# Ethernet.net
KiCad netlist of a schematic drawn in Altium Designer
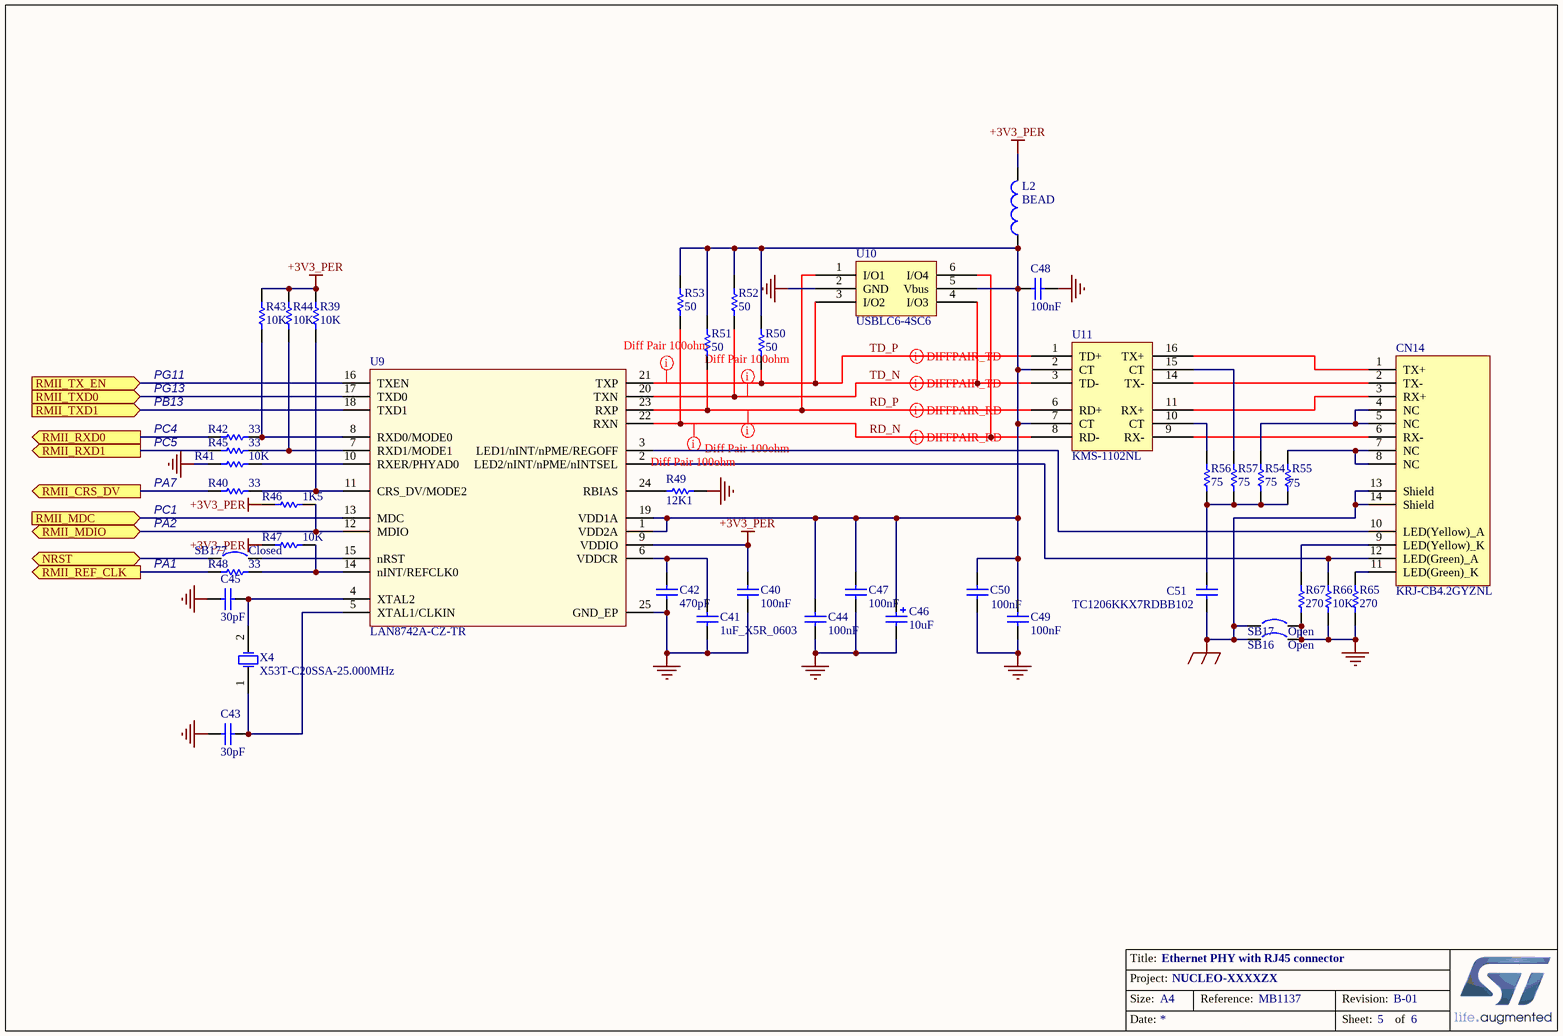
[diagram p0: Ethernet.SchDoc]

(export (version "E")
  (design (tool "Eeschema 10.0.6"))
  (components
    (comp (ref "C40")
      (value "100nF")
      (footprint "0603C")
      (description "Capacitor 0402 / 0603 / 0805")
      (libsource (lib "MCD_TOOLS") (part "Capacitor_ST"))
    )
    (comp (ref "C41")
      (value "1uF_X5R_0603")
      (footprint "0603C")
      (description "0603  X5R 1µF")
      (fields (field (name "TOLERANCE") "10%"))
      (libsource (lib "MB963_1") (part "CAP SMD 0603  X5R 1µF 25V 10%"))
    )
    (comp (ref "C42")
      (value "470pF")
      (footprint "0603C")
      (description "Capacitor 0402 / 0603 / 0805")
      (libsource (lib "MCD_TOOLS") (part "Capacitor_ST"))
    )
    (comp (ref "C43")
      (value "30pF")
      (footprint "0603C")
      (description "Capacitor 0402 / 0603 / 0805")
      (libsource (lib "MCD_TOOLS") (part "Capacitor_ST"))
    )
    (comp (ref "C44")
      (value "100nF")
      (footprint "0603C")
      (description "Capacitor 0402 / 0603 / 0805")
      (libsource (lib "MCD_TOOLS") (part "Capacitor_ST"))
    )
    (comp (ref "C45")
      (value "30pF")
      (footprint "0603C")
      (description "Capacitor 0402 / 0603 / 0805")
      (libsource (lib "MCD_TOOLS") (part "Capacitor_ST"))
    )
    (comp (ref "C46")
      (value "10uF")
      (footprint "TAN-A")
      (description "Polarized Capacitor,10uF,10V,10%,typeA,VISHAY")
      (libsource (lib "MCD_TOOLS") (part "Cap_10uF_POL_10%_TANA"))
    )
    (comp (ref "C47")
      (value "100nF")
      (footprint "0603C")
      (description "Capacitor 0402 / 0603 / 0805")
      (libsource (lib "MCD_TOOLS") (part "Capacitor_ST"))
    )
    (comp (ref "C48")
      (value "100nF")
      (footprint "0603C")
      (description "Capacitor 0402 / 0603 / 0805")
      (libsource (lib "MCD_TOOLS") (part "Capacitor_ST"))
    )
    (comp (ref "C49")
      (value "100nF")
      (footprint "0603C")
      (description "Capacitor 0402 / 0603 / 0805")
      (libsource (lib "MCD_TOOLS") (part "Capacitor_ST"))
    )
    (comp (ref "C50")
      (value "100nF")
      (footprint "0603C")
      (description "Capacitor 0402 / 0603 / 0805")
      (libsource (lib "MCD_TOOLS") (part "Capacitor_ST"))
    )
    (comp (ref "C51")
      (value "TC1206KKX7RDBB102")
      (footprint "1206C")
      (description "Capacitor 0402 / 0603 / 0805/ 1206")
      (libsource (lib "MCD_TOOLS") (part "Capacitor_ST"))
    )
    (comp (ref "CN14")
      (value "KRJ-CB4.2GYZNL")
      (footprint "RJ45_KRJ-CB4.2GYZNL")
      (description "100 Base-TX (Fast Ethernet) SMD RJ45 single port (1x1) with LEDS Integrated Magnetics Connector")
      (libsource (lib "MB1137") (part "KRJ-CB4.2GYZNL"))
    )
    (comp (ref "L2")
      (value "BEAD")
      (footprint "0603L")
      (description "Inductor")
      (fields (field (name "PUBLISHER") "Altium Limited"))
      (libsource (lib "Miscellaneous Devices") (part "Inductor"))
    )
    (comp (ref "R39")
      (value "10K")
      (footprint "0603R")
      (description "Resistor 0402 / 0603 / 0805")
      (libsource (lib "Miscellaneous Devices") (part "Res1"))
    )
    (comp (ref "R40")
      (value "33")
      (footprint "0603R")
      (description "Resistor,33,0402,1%,YAGEO")
      (libsource (lib "MCD_TOOLS") (part "Res_33_1%_0402"))
    )
    (comp (ref "R41")
      (value "10K")
      (footprint "0603R")
      (description "Resistor 0402 / 0603 / 0805")
      (libsource (lib "Miscellaneous Devices") (part "Res1"))
    )
    (comp (ref "R42")
      (value "33")
      (footprint "0603R")
      (description "Resistor,33,0402,1%,YAGEO")
      (libsource (lib "MCD_TOOLS") (part "Res_33_1%_0402"))
    )
    (comp (ref "R43")
      (value "10K")
      (footprint "0603R")
      (description "Resistor 0402 / 0603 / 0805")
      (libsource (lib "Miscellaneous Devices") (part "Res1"))
    )
    (comp (ref "R44")
      (value "10K")
      (footprint "0603R")
      (description "Resistor 0402 / 0603 / 0805")
      (libsource (lib "Miscellaneous Devices") (part "Res1"))
    )
    (comp (ref "R45")
      (value "33")
      (footprint "0603R")
      (description "Resistor,33,0402,1%,YAGEO")
      (libsource (lib "MCD_TOOLS") (part "Res_33_1%_0402"))
    )
    (comp (ref "R46")
      (value "1K5")
      (footprint "0603R")
      (description "Resistor,1K5,0402,1%,YAGEO")
      (libsource (lib "MCD_TOOLS") (part "Res_1K5_1%_0402"))
    )
    (comp (ref "R47")
      (value "10K")
      (footprint "0603R")
      (description "Resistor 0402 / 0603 / 0805")
      (libsource (lib "Miscellaneous Devices") (part "Res1"))
    )
    (comp (ref "R48")
      (value "33")
      (footprint "0603R")
      (description "Resistor,33,0402,1%,YAGEO")
      (libsource (lib "MCD_TOOLS") (part "Res_33_1%_0402"))
    )
    (comp (ref "R49")
      (value "12K1")
      (footprint "0603R")
      (description "Resistor,12K1,0603,1%,VISHAY")
      (libsource (lib "MCD_TOOLS") (part "Res_12K1_1%_0603"))
    )
    (comp (ref "R50")
      (value "50")
      (footprint "0603R")
      (description "Resistor,50,0603,1%,YAGEO")
      (libsource (lib "MB1137") (part "Res_50_1%_0603"))
    )
    (comp (ref "R51")
      (value "50")
      (footprint "0603R")
      (description "Resistor,50,0603,1%,YAGEO")
      (libsource (lib "MB1137") (part "Res_50_1%_0603"))
    )
    (comp (ref "R52")
      (value "50")
      (footprint "0603R")
      (description "Resistor,50,0603,1%,YAGEO")
      (libsource (lib "MB1137") (part "Res_50_1%_0603"))
    )
    (comp (ref "R53")
      (value "50")
      (footprint "0603R")
      (description "Resistor,50,0603,1%,YAGEO")
      (libsource (lib "MB1137") (part "Res_50_1%_0603"))
    )
    (comp (ref "R54")
      (value "75")
      (footprint "0603R")
      (description "Resistor,75,0603,1%,YAGEO")
      (libsource (lib "MB1137") (part "Res_75_1%_0603"))
    )
    (comp (ref "R55")
      (value "75")
      (footprint "0603R")
      (description "Resistor,75,0603,1%,YAGEO")
      (libsource (lib "MB1137") (part "Res_75_1%_0603"))
    )
    (comp (ref "R56")
      (value "75")
      (footprint "0603R")
      (description "Resistor,75,0603,1%,YAGEO")
      (libsource (lib "MB1137") (part "Res_75_1%_0603"))
    )
    (comp (ref "R57")
      (value "75")
      (footprint "0603R")
      (description "Resistor,75,0603,1%,YAGEO")
      (libsource (lib "MB1137") (part "Res_75_1%_0603"))
    )
    (comp (ref "R65")
      (value "270")
      (footprint "0603R")
      (description "Resistor 0402 / 0603 / 0805")
      (libsource (lib "Miscellaneous Devices") (part "Res1"))
    )
    (comp (ref "R66")
      (value "10K")
      (footprint "0603R")
      (description "Resistor 0402 / 0603 / 0805")
      (libsource (lib "Miscellaneous Devices") (part "Res1"))
    )
    (comp (ref "R67")
      (value "270")
      (footprint "0603R")
      (description "Resistor 0402 / 0603 / 0805")
      (libsource (lib "Miscellaneous Devices") (part "Res1"))
    )
    (comp (ref "SB16")
      (value "Open")
      (footprint "SB_0603")
      (description "Circuit Breaker")
      (fields (field (name "PUBLISHER") "Altium Limited"))
      (libsource (lib "MB1167") (part "Circuit Breaker"))
    )
    (comp (ref "SB17")
      (value "Open")
      (footprint "SB_0603")
      (description "Circuit Breaker")
      (fields (field (name "PUBLISHER") "Altium Limited"))
      (libsource (lib "MB1167") (part "Circuit Breaker"))
    )
    (comp (ref "SB177")
      (value "Closed")
      (footprint "SB_0603")
      (description "Circuit Breaker")
      (fields (field (name "PUBLISHER") "Altium Limited"))
      (libsource (lib "MB1167") (part "Circuit Breaker_close"))
    )
    (comp (ref "U9")
      (value "LAN8742A-CZ-TR")
      (footprint "QFN24_0R5_4X4")
      (libsource (lib "MB1137") (part "LAN8742A-CZ-TR"))
    )
    (comp (ref "U10")
      (value "USBLC6-4SC6")
      (footprint "SOT23-6L")
      (libsource (lib "MB1137_1") (part "USBLC6-4SC6"))
    )
    (comp (ref "U11")
      (value "KMS-1102NL")
      (footprint "Transformer")
      (libsource (lib "MB1137") (part "KMS-1102NL"))
    )
    (comp (ref "X4")
      (value "X53T-C20SSA-25.000MHz")
      (footprint "XTAL_2SM_5R0X3R2")
      (description "Crystal Oscillator")
      (fields (field (name "PUBLISHER") "Altium Limited"))
      (libsource (lib "MB1137") (part "XTAL_5032"))
    )
  )
  (nets
    (net (code "1") (name "+3V3_PER") (class "Default")
      (node (ref "C40") (pin "2") (pinfunction "2_2") (pintype "passive"))
      (node (ref "L2") (pin "2") (pinfunction "2_2") (pintype "passive"))
      (node (ref "R39") (pin "1") (pinfunction "1_1") (pintype "passive"))
      (node (ref "R43") (pin "1") (pinfunction "1_1") (pintype "passive"))
      (node (ref "R44") (pin "1") (pinfunction "1_1") (pintype "passive"))
      (node (ref "R46") (pin "2") (pinfunction "2_2") (pintype "passive"))
      (node (ref "R47") (pin "1") (pinfunction "1_1") (pintype "passive"))
      (node (ref "U9") (pin "9") (pinfunction "VDDIO_9") (pintype "passive"))
    )
    (net (code "2") (name "/NRST") (class "Default")
      (node (ref "SB177") (pin "1") (pinfunction "1_1") (pintype "passive"))
    )
    (net (code "3") (name "/RD_N") (class "Default")
      (node (ref "R53") (pin "1") (pinfunction "1_1") (pintype "passive"))
      (node (ref "U10") (pin "6") (pinfunction "I/O4_6") (pintype "passive"))
      (node (ref "U11") (pin "8") (pinfunction "RD-_8") (pintype "passive"))
      (node (ref "U9") (pin "22") (pinfunction "RXN_22") (pintype "passive"))
    )
    (net (code "4") (name "/RD_P") (class "Default")
      (node (ref "R51") (pin "1") (pinfunction "1_1") (pintype "passive"))
      (node (ref "U10") (pin "1") (pinfunction "I/O1_1") (pintype "passive"))
      (node (ref "U11") (pin "6") (pinfunction "RD+_6") (pintype "passive"))
      (node (ref "U9") (pin "23") (pinfunction "RXP_23") (pintype "passive"))
    )
    (net (code "5") (name "/RMII_CRS_DV") (class "Default")
      (node (ref "R40") (pin "2") (pinfunction "2_2") (pintype "passive"))
    )
    (net (code "6") (name "/RMII_MDC") (class "Default")
      (node (ref "U9") (pin "13") (pinfunction "MDC_13") (pintype "passive"))
    )
    (net (code "7") (name "/RMII_MDIO") (class "Default")
      (node (ref "R46") (pin "1") (pinfunction "1_1") (pintype "passive"))
      (node (ref "U9") (pin "12") (pinfunction "MDIO_12") (pintype "passive"))
    )
    (net (code "8") (name "/RMII_REF_CLK") (class "Default")
      (node (ref "R48") (pin "2") (pinfunction "2_2") (pintype "passive"))
    )
    (net (code "9") (name "/RMII_RXD0") (class "Default")
      (node (ref "R42") (pin "2") (pinfunction "2_2") (pintype "passive"))
    )
    (net (code "10") (name "/RMII_RXD1") (class "Default")
      (node (ref "R45") (pin "2") (pinfunction "2_2") (pintype "passive"))
    )
    (net (code "11") (name "/RMII_TXD0") (class "Default")
      (node (ref "U9") (pin "17") (pinfunction "TXD0_17") (pintype "passive"))
    )
    (net (code "12") (name "/RMII_TXD1") (class "Default")
      (node (ref "U9") (pin "18") (pinfunction "TXD1_18") (pintype "passive"))
    )
    (net (code "13") (name "/RMII_TX_EN") (class "Default")
      (node (ref "U9") (pin "16") (pinfunction "TXEN_16") (pintype "passive"))
    )
    (net (code "14") (name "/TD_N") (class "Default")
      (node (ref "R52") (pin "1") (pinfunction "1_1") (pintype "passive"))
      (node (ref "U10") (pin "4") (pinfunction "I/O3_4") (pintype "passive"))
      (node (ref "U11") (pin "3") (pinfunction "TD-_3") (pintype "passive"))
      (node (ref "U9") (pin "20") (pinfunction "TXN_20") (pintype "passive"))
    )
    (net (code "15") (name "/TD_P") (class "Default")
      (node (ref "R50") (pin "1") (pinfunction "1_1") (pintype "passive"))
      (node (ref "U10") (pin "3") (pinfunction "I/O2_3") (pintype "passive"))
      (node (ref "U11") (pin "1") (pinfunction "TD+_1") (pintype "passive"))
      (node (ref "U9") (pin "21") (pinfunction "TXP_21") (pintype "passive"))
    )
    (net (code "16") (name "EGND") (class "Default")
      (node (ref "C51") (pin "1") (pinfunction "1_1") (pintype "passive"))
      (node (ref "CN14") (pin "13") (pinfunction "Shield_13") (pintype "passive"))
      (node (ref "CN14") (pin "14") (pinfunction "Shield_14") (pintype "passive"))
      (node (ref "SB16") (pin "1") (pinfunction "1_1") (pintype "passive"))
      (node (ref "SB17") (pin "1") (pinfunction "1_1") (pintype "passive"))
    )
    (net (code "17") (name "GND") (class "Default")
      (node (ref "C40") (pin "1") (pinfunction "1_1") (pintype "passive"))
      (node (ref "C41") (pin "2") (pinfunction "2_2") (pintype "passive"))
      (node (ref "C42") (pin "1") (pinfunction "1_1") (pintype "passive"))
      (node (ref "C43") (pin "2") (pinfunction "2_2") (pintype "passive"))
      (node (ref "C44") (pin "1") (pinfunction "1_1") (pintype "passive"))
      (node (ref "C45") (pin "2") (pinfunction "2_2") (pintype "passive"))
      (node (ref "C46") (pin "2") (pinfunction "2_2") (pintype "passive"))
      (node (ref "C47") (pin "1") (pinfunction "1_1") (pintype "passive"))
      (node (ref "C48") (pin "1") (pinfunction "1_1") (pintype "passive"))
      (node (ref "C49") (pin "1") (pinfunction "1_1") (pintype "passive"))
      (node (ref "C50") (pin "1") (pinfunction "1_1") (pintype "passive"))
      (node (ref "R41") (pin "2") (pinfunction "2_2") (pintype "passive"))
      (node (ref "R49") (pin "2") (pinfunction "2_2") (pintype "passive"))
      (node (ref "R65") (pin "2") (pinfunction "2_2") (pintype "passive"))
      (node (ref "R66") (pin "2") (pinfunction "2_2") (pintype "passive"))
      (node (ref "R67") (pin "2") (pinfunction "2_2") (pintype "passive"))
      (node (ref "SB16") (pin "2") (pinfunction "2_2") (pintype "passive"))
      (node (ref "SB17") (pin "2") (pinfunction "2_2") (pintype "passive"))
      (node (ref "U10") (pin "2") (pinfunction "GND_2") (pintype "passive"))
      (node (ref "U9") (pin "25") (pinfunction "GND_EP_25") (pintype "passive"))
    )
    (net (code "18") (name "Net-(C51-Pad2)") (class "Default")
      (node (ref "C51") (pin "2") (pinfunction "2_2") (pintype "passive"))
      (node (ref "R54") (pin "1") (pinfunction "1_1") (pintype "passive"))
      (node (ref "R55") (pin "1") (pinfunction "1_1") (pintype "passive"))
      (node (ref "R56") (pin "1") (pinfunction "1_1") (pintype "passive"))
      (node (ref "R57") (pin "1") (pinfunction "1_1") (pintype "passive"))
    )
    (net (code "19") (name "Net-(CN14-LED(Green)_A)") (class "Default")
      (node (ref "CN14") (pin "12") (pinfunction "LED(Green)_A_12") (pintype "passive"))
      (node (ref "R66") (pin "1") (pinfunction "1_1") (pintype "passive"))
      (node (ref "U9") (pin "2") (pinfunction "LED2/nINT/nPME/nINTSEL_2") (pintype "passive"))
    )
    (net (code "20") (name "Net-(CN14-LED(Green)_K)") (class "Default")
      (node (ref "CN14") (pin "11") (pinfunction "LED(Green)_K_11") (pintype "passive"))
      (node (ref "R65") (pin "1") (pinfunction "1_1") (pintype "passive"))
    )
    (net (code "21") (name "Net-(CN14-LED(Yellow)_A)") (class "Default")
      (node (ref "CN14") (pin "10") (pinfunction "LED(Yellow)_A_10") (pintype "passive"))
      (node (ref "U9") (pin "3") (pinfunction "LED1/nINT/nPME/REGOFF_3") (pintype "passive"))
    )
    (net (code "22") (name "Net-(CN14-LED(Yellow)_K)") (class "Default")
      (node (ref "CN14") (pin "9") (pinfunction "LED(Yellow)_K_9") (pintype "passive"))
      (node (ref "R67") (pin "1") (pinfunction "1_1") (pintype "passive"))
    )
    (net (code "23") (name "Net-(CN14-NC-Pad4)") (class "Default")
      (node (ref "CN14") (pin "4") (pinfunction "NC_4") (pintype "passive"))
      (node (ref "CN14") (pin "5") (pinfunction "NC_5") (pintype "passive"))
      (node (ref "R54") (pin "2") (pinfunction "2_2") (pintype "passive"))
    )
    (net (code "24") (name "Net-(CN14-NC-Pad7)") (class "Default")
      (node (ref "CN14") (pin "7") (pinfunction "NC_7") (pintype "passive"))
      (node (ref "CN14") (pin "8") (pinfunction "NC_8") (pintype "passive"))
      (node (ref "R55") (pin "2") (pinfunction "2_2") (pintype "passive"))
    )
    (net (code "25") (name "Net-(CN14-RX+)") (class "Default")
      (node (ref "CN14") (pin "3") (pinfunction "RX+_3") (pintype "passive"))
      (node (ref "U11") (pin "11") (pinfunction "RX+_11") (pintype "passive"))
    )
    (net (code "26") (name "Net-(CN14-RX-)") (class "Default")
      (node (ref "CN14") (pin "6") (pinfunction "RX-_6") (pintype "passive"))
      (node (ref "U11") (pin "9") (pinfunction "RX-_9") (pintype "passive"))
    )
    (net (code "27") (name "Net-(CN14-TX+)") (class "Default")
      (node (ref "CN14") (pin "1") (pinfunction "TX+_1") (pintype "passive"))
      (node (ref "U11") (pin "16") (pinfunction "TX+_16") (pintype "passive"))
    )
    (net (code "28") (name "Net-(CN14-TX-)") (class "Default")
      (node (ref "CN14") (pin "2") (pinfunction "TX-_2") (pintype "passive"))
      (node (ref "U11") (pin "14") (pinfunction "TX-_14") (pintype "passive"))
    )
    (net (code "29") (name "Net-(R56-Pad2)") (class "Default")
      (node (ref "R56") (pin "2") (pinfunction "2_2") (pintype "passive"))
      (node (ref "U11") (pin "10") (pinfunction "CT_10") (pintype "passive"))
    )
    (net (code "30") (name "Net-(R57-Pad2)") (class "Default")
      (node (ref "R57") (pin "2") (pinfunction "2_2") (pintype "passive"))
      (node (ref "U11") (pin "15") (pinfunction "CT_15") (pintype "passive"))
    )
    (net (code "31") (name "Net-(U9-CRS_DV{slash}MODE2)") (class "Default")
      (node (ref "R39") (pin "2") (pinfunction "2_2") (pintype "passive"))
      (node (ref "R40") (pin "1") (pinfunction "1_1") (pintype "passive"))
      (node (ref "U9") (pin "11") (pinfunction "CRS_DV/MODE2_11") (pintype "passive"))
    )
    (net (code "32") (name "Net-(U9-RBIAS)") (class "Default")
      (node (ref "R49") (pin "1") (pinfunction "1_1") (pintype "passive"))
      (node (ref "U9") (pin "24") (pinfunction "RBIAS_24") (pintype "passive"))
    )
    (net (code "33") (name "Net-(U9-RXD0{slash}MODE0)") (class "Default")
      (node (ref "R42") (pin "1") (pinfunction "1_1") (pintype "passive"))
      (node (ref "R43") (pin "2") (pinfunction "2_2") (pintype "passive"))
      (node (ref "U9") (pin "8") (pinfunction "RXD0/MODE0_8") (pintype "passive"))
    )
    (net (code "34") (name "Net-(U9-RXD1{slash}MODE1)") (class "Default")
      (node (ref "R44") (pin "2") (pinfunction "2_2") (pintype "passive"))
      (node (ref "R45") (pin "1") (pinfunction "1_1") (pintype "passive"))
      (node (ref "U9") (pin "7") (pinfunction "RXD1/MODE1_7") (pintype "passive"))
    )
    (net (code "35") (name "Net-(U9-RXER{slash}PHYAD0)") (class "Default")
      (node (ref "R41") (pin "1") (pinfunction "1_1") (pintype "passive"))
      (node (ref "U9") (pin "10") (pinfunction "RXER/PHYAD0_10") (pintype "passive"))
    )
    (net (code "36") (name "Net-(U9-VDDCR)") (class "Default")
      (node (ref "C41") (pin "1") (pinfunction "1_1") (pintype "passive"))
      (node (ref "C42") (pin "2") (pinfunction "2_2") (pintype "passive"))
      (node (ref "U9") (pin "6") (pinfunction "VDDCR_6") (pintype "passive"))
    )
    (net (code "37") (name "Net-(U9-XTAL1{slash}CLKIN)") (class "Default")
      (node (ref "C43") (pin "1") (pinfunction "1_1") (pintype "passive"))
      (node (ref "U9") (pin "5") (pinfunction "XTAL1/CLKIN_5") (pintype "passive"))
      (node (ref "X4") (pin "1") (pinfunction "OSC1_1") (pintype "passive"))
    )
    (net (code "38") (name "Net-(U9-XTAL2)") (class "Default")
      (node (ref "C45") (pin "1") (pinfunction "1_1") (pintype "passive"))
      (node (ref "U9") (pin "4") (pinfunction "XTAL2_4") (pintype "passive"))
      (node (ref "X4") (pin "2") (pinfunction "OSC2_2") (pintype "passive"))
    )
    (net (code "39") (name "Net-(U9-nINT{slash}REFCLK0)") (class "Default")
      (node (ref "R47") (pin "2") (pinfunction "2_2") (pintype "passive"))
      (node (ref "R48") (pin "1") (pinfunction "1_1") (pintype "passive"))
      (node (ref "U9") (pin "14") (pinfunction "nINT/REFCLK0_14") (pintype "passive"))
    )
    (net (code "40") (name "Net-(U9-nRST)") (class "Default")
      (node (ref "SB177") (pin "2") (pinfunction "2_2") (pintype "passive"))
      (node (ref "U9") (pin "15") (pinfunction "nRST_15") (pintype "passive"))
    )
    (net (code "41") (name "Net-(U10-Vbus)") (class "Default")
      (node (ref "C44") (pin "2") (pinfunction "2_2") (pintype "passive"))
      (node (ref "C46") (pin "1") (pinfunction "1_1") (pintype "passive"))
      (node (ref "C47") (pin "2") (pinfunction "2_2") (pintype "passive"))
      (node (ref "C48") (pin "2") (pinfunction "2_2") (pintype "passive"))
      (node (ref "C49") (pin "2") (pinfunction "2_2") (pintype "passive"))
      (node (ref "C50") (pin "2") (pinfunction "2_2") (pintype "passive"))
      (node (ref "L2") (pin "1") (pinfunction "1_1") (pintype "passive"))
      (node (ref "R50") (pin "2") (pinfunction "2_2") (pintype "passive"))
      (node (ref "R51") (pin "2") (pinfunction "2_2") (pintype "passive"))
      (node (ref "R52") (pin "2") (pinfunction "2_2") (pintype "passive"))
      (node (ref "R53") (pin "2") (pinfunction "2_2") (pintype "passive"))
      (node (ref "U10") (pin "5") (pinfunction "Vbus_5") (pintype "passive"))
      (node (ref "U11") (pin "2") (pinfunction "CT_2") (pintype "passive"))
      (node (ref "U11") (pin "7") (pinfunction "CT_7") (pintype "passive"))
      (node (ref "U9") (pin "1") (pinfunction "VDD2A_1") (pintype "passive"))
      (node (ref "U9") (pin "19") (pinfunction "VDD1A_19") (pintype "passive"))
    )
  )
)
